# Humi_IOT.net
KiCad netlist of a schematic drawn in Altium Designer
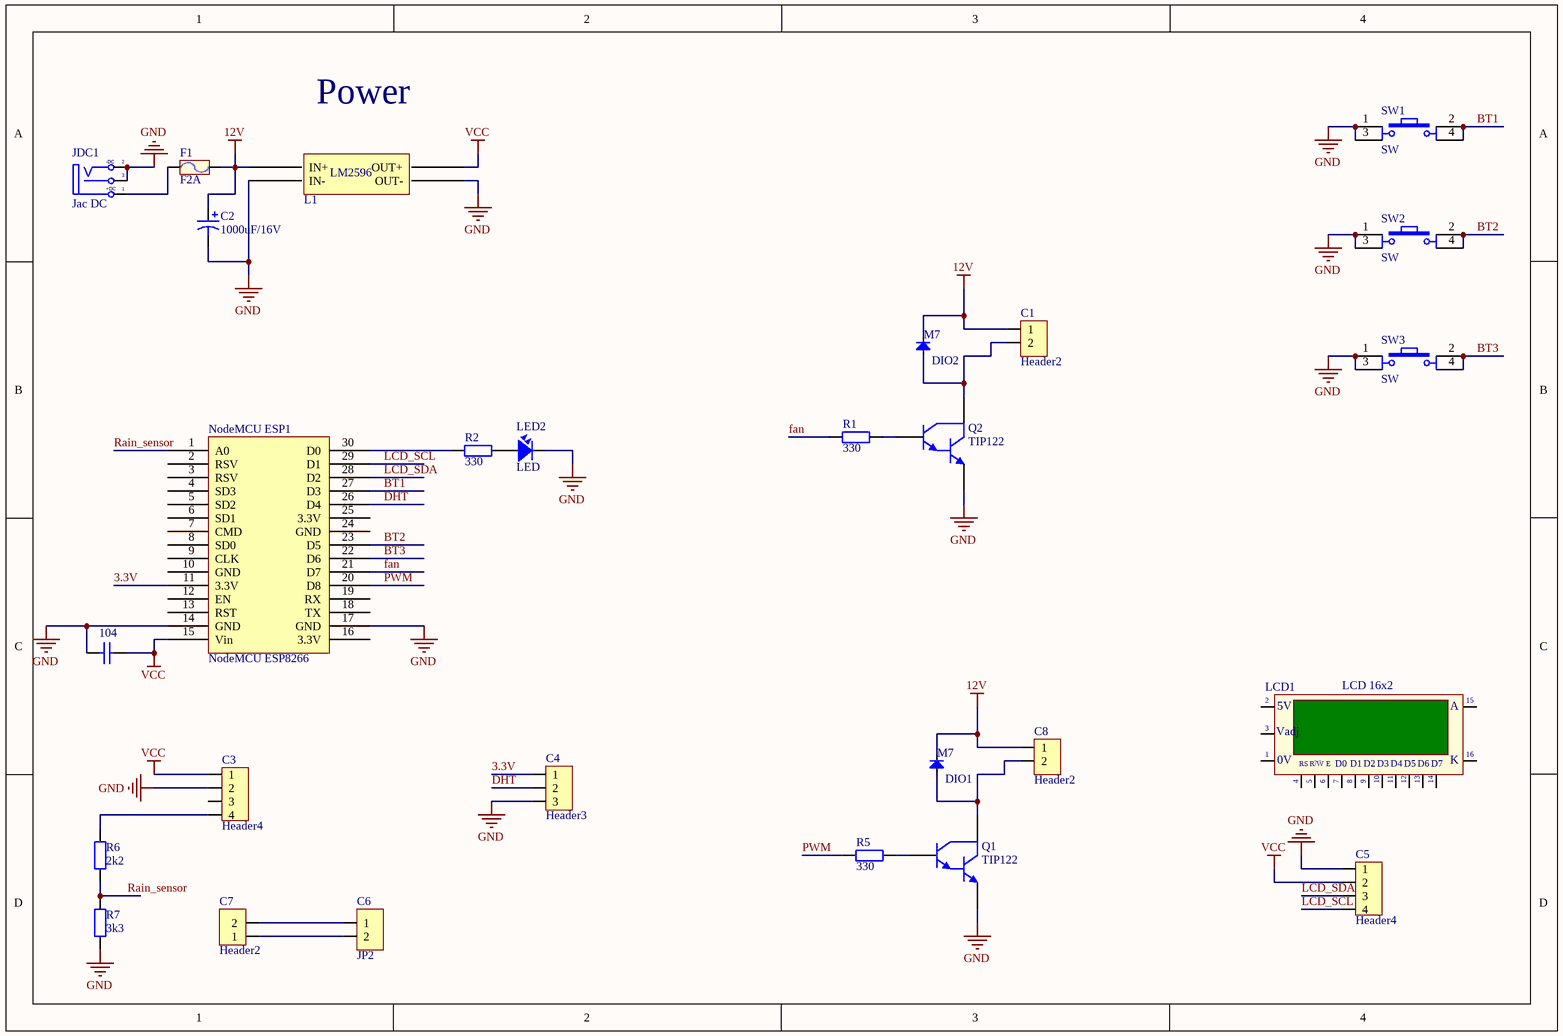
[diagram p0: Humi_IOT.SchDoc]

(export (version "E")
  (design (tool "Eeschema 10.0.6"))
  (components
    (comp (ref "104")
      (value "Capacitor Ceramic")
      (footprint "C0805")
      (description "Capacitor")
      (fields (field (name "PUBLISHER") "Altium Limited"))
      (libsource (lib "My Library") (part "CapSMD"))
    )
    (comp (ref "C1")
      (value "Header2")
      (footprint "Header2")
      (description "Header IDC, 2 x 1 Pin Vertical 2.54mm Pitch (Non-Boxed, Male)")
      (fields
        (field (name "MANUFACTURER") "Würth Elektronik eiSos GmbH")
        (field (name "PARTNO") "613002143121")
        (field (name "CREATED BY") "Karrer Zheng")
      )
      (libsource (lib "My Library") (part "Header2"))
    )
    (comp (ref "C2")
      (value "1000uF/16V")
      (footprint "C10mm")
      (description "Polarized Capacitor (Axial)")
      (fields (field (name "PUBLISHER") "Altium Limited"))
      (libsource (lib "My Library") (part "Cap Pol 12mm"))
    )
    (comp (ref "C3")
      (value "Header4")
      (footprint "HDR4")
      (description "Header IDC, 4 x 1 Pin Vertical 2.54mm Pitch (Non-Boxed, Male)")
      (fields
        (field (name "MANUFACTURER") "Würth Elektronik eiSos GmbH")
        (field (name "PARTNO") "613002143121")
        (field (name "CREATED BY") "Karrer Zheng")
      )
      (libsource (lib "My Library") (part "Header4"))
    )
    (comp (ref "C4")
      (value "Header3")
      (footprint "Header3")
      (description "Header IDC, 3 x 1 Pin Vertical 2.54mm Pitch (Non-Boxed, Male)")
      (fields
        (field (name "MANUFACTURER") "Würth Elektronik eiSos GmbH")
        (field (name "PARTNO") "613002143121")
        (field (name "CREATED BY") "Karrer Zheng")
      )
      (libsource (lib "My Library") (part "Header3"))
    )
    (comp (ref "C5")
      (value "Header4")
      (footprint "HDR4")
      (description "Header IDC, 4 x 1 Pin Vertical 2.54mm Pitch (Non-Boxed, Male)")
      (fields
        (field (name "MANUFACTURER") "Würth Elektronik eiSos GmbH")
        (field (name "PARTNO") "613002143121")
        (field (name "CREATED BY") "Karrer Zheng")
      )
      (libsource (lib "My Library") (part "Header4"))
    )
    (comp (ref "C6")
      (value "JP2")
      (footprint "JP2-C1T")
      (description "WR-PHD 2.54 mm Angled Socket Header")
      (fields
        (field (name "MANUFACTURER") "Würth Elektronik eiSos GmbH")
        (field (name "PARTNO") "613002143121")
        (field (name "CREATED BY") "Karrer Zheng")
      )
      (libsource (lib "My Library") (part "JP2"))
    )
    (comp (ref "C7")
      (value "Header2")
      (footprint "Header2")
      (description "Header IDC, 2 x 1 Pin Vertical 2.54mm Pitch (Non-Boxed, Male)")
      (fields
        (field (name "MANUFACTURER") "Würth Elektronik eiSos GmbH")
        (field (name "PARTNO") "613002143121")
        (field (name "CREATED BY") "Karrer Zheng")
      )
      (libsource (lib "") (part "Header2_1"))
    )
    (comp (ref "C8")
      (value "Header2")
      (footprint "Header2")
      (description "Header IDC, 2 x 1 Pin Vertical 2.54mm Pitch (Non-Boxed, Male)")
      (fields
        (field (name "MANUFACTURER") "Würth Elektronik eiSos GmbH")
        (field (name "PARTNO") "613002143121")
        (field (name "CREATED BY") "Karrer Zheng")
      )
      (libsource (lib "My Library") (part "Header2"))
    )
    (comp (ref "DIO1")
      (value "M7")
      (footprint "DIO-SMD-106")
      (description "Default Diode")
      (fields (field (name "PUBLISHER") "Altium Limited"))
      (libsource (lib "My Library (1)") (part "Diode SMD"))
    )
    (comp (ref "DIO2")
      (value "M7")
      (footprint "DIO-SMD-106")
      (description "Default Diode")
      (fields (field (name "PUBLISHER") "Altium Limited"))
      (libsource (lib "My Library (1)") (part "Diode SMD"))
    )
    (comp (ref "F1")
      (value "F2A")
      (footprint "Fuse")
      (description "Fuse")
      (fields (field (name "DESIGNED BY") "VanDungEvn"))
      (libsource (lib "My Library") (part "Fuse"))
    )
    (comp (ref "JDC1")
      (value "Jac DC")
      (footprint "DC-IN")
      (description "Jac DC input")
      (libsource (lib "My Library") (part "DCIN"))
    )
    (comp (ref "L1")
      (value "BUCK_LM2596")
      (footprint "BUCK_LM2596")
      (libsource (lib "BUCK_LM2596_Sch") (part "BUCK_LM2596"))
    )
    (comp (ref "LCD1")
      (value "LCD 16x2")
      (footprint "LCD16X2N")
      (libsource (lib "My library altium") (part "LCD"))
    )
    (comp (ref "LED2")
      (value "LED")
      (footprint "LED-5 GRe")
      (description "LED Single colour Green and Red")
      (libsource (lib "My Library") (part "LED"))
    )
    (comp (ref "NodeMCU ESP1")
      (value "NodeMCU ESP8266")
      (footprint "NodeMCU ESP8266")
      (libsource (lib "Phieu_Du") (part "NodeMCU ESP8266"))
    )
    (comp (ref "Q1")
      (value "TIP122")
      (footprint "QTO-220")
      (description "Darlington Silicon Power NPN Transistor, 8 Amp, 100 Volts and 65 Watts")
      (libsource (lib "My Library (1)") (part "TIP122"))
    )
    (comp (ref "Q2")
      (value "TIP122")
      (footprint "QTO-220")
      (description "Darlington Silicon Power NPN Transistor, 8 Amp, 100 Volts and 65 Watts")
      (libsource (lib "My Library (1)") (part "TIP122"))
    )
    (comp (ref "R1")
      (value "330")
      (footprint "DIEN TRO 0805")
      (description "Resistor SMD 0805")
      (fields (field (name "PUBLISHER") "Altium Limited"))
      (libsource (lib "My Library (1)") (part "R0805"))
    )
    (comp (ref "R2")
      (value "330")
      (footprint "DIEN TRO 0805")
      (description "Resistor SMD 0805")
      (fields (field (name "PUBLISHER") "Altium Limited"))
      (libsource (lib "My Library (1)") (part "R0805"))
    )
    (comp (ref "R5")
      (value "330")
      (footprint "DIEN TRO 0805")
      (description "Resistor SMD 0805")
      (fields (field (name "PUBLISHER") "Altium Limited"))
      (libsource (lib "My Library (1)") (part "R0805"))
    )
    (comp (ref "R6")
      (value "2k2")
      (footprint "DIEN TRO 0805")
      (description "Resistor SMD 0805")
      (fields (field (name "PUBLISHER") "Altium Limited"))
      (libsource (lib "") (part "R0805_1"))
    )
    (comp (ref "R7")
      (value "3k3")
      (footprint "DIEN TRO 0805")
      (description "Resistor SMD 0805")
      (fields (field (name "PUBLISHER") "Altium Limited"))
      (libsource (lib "") (part "R0805_1"))
    )
    (comp (ref "SW1")
      (value "SW")
      (footprint "SW4")
      (description "Switch button 4 pin")
      (libsource (lib "My Library (1)") (part "SW4"))
    )
    (comp (ref "SW2")
      (value "SW")
      (footprint "SW4")
      (description "Switch button 4 pin")
      (libsource (lib "My Library (1)") (part "SW4"))
    )
    (comp (ref "SW3")
      (value "SW")
      (footprint "SW4")
      (description "Switch button 4 pin")
      (libsource (lib "My Library (1)") (part "SW4"))
    )
  )
  (nets
    (net (code "1") (name "/3.3V") (class "Default")
      (node (ref "C4") (pin "1") (pinfunction "1_1") (pintype "passive"))
      (node (ref "NodeMCU ESP1") (pin "11") (pinfunction "3.3V_11") (pintype "passive"))
    )
    (net (code "2") (name "/BT1") (class "Default")
      (node (ref "NodeMCU ESP1") (pin "27") (pinfunction "D3_27") (pintype "passive"))
      (node (ref "SW1") (pin "2") (pintype "passive"))
      (node (ref "SW1") (pin "4") (pintype "passive"))
    )
    (net (code "3") (name "/BT2") (class "Default")
      (node (ref "NodeMCU ESP1") (pin "23") (pinfunction "D5_23") (pintype "passive"))
      (node (ref "SW2") (pin "2") (pintype "passive"))
      (node (ref "SW2") (pin "4") (pintype "passive"))
    )
    (net (code "4") (name "/BT3") (class "Default")
      (node (ref "NodeMCU ESP1") (pin "22") (pinfunction "D6_22") (pintype "passive"))
      (node (ref "SW3") (pin "2") (pintype "passive"))
      (node (ref "SW3") (pin "4") (pintype "passive"))
    )
    (net (code "5") (name "/DHT") (class "Default")
      (node (ref "C4") (pin "2") (pinfunction "2_2") (pintype "passive"))
      (node (ref "NodeMCU ESP1") (pin "26") (pinfunction "D4_26") (pintype "passive"))
    )
    (net (code "6") (name "/LCD_SCL") (class "Default")
      (node (ref "C5") (pin "4") (pinfunction "4_4") (pintype "passive"))
      (node (ref "NodeMCU ESP1") (pin "29") (pinfunction "D1_29") (pintype "passive"))
    )
    (net (code "7") (name "/LCD_SDA") (class "Default")
      (node (ref "C5") (pin "3") (pinfunction "3_3") (pintype "passive"))
      (node (ref "NodeMCU ESP1") (pin "28") (pinfunction "D2_28") (pintype "passive"))
    )
    (net (code "8") (name "/PWM") (class "Default")
      (node (ref "NodeMCU ESP1") (pin "20") (pinfunction "D8_20") (pintype "passive"))
      (node (ref "R5") (pin "2") (pinfunction "2_2") (pintype "passive"))
    )
    (net (code "9") (name "/Rain_sensor") (class "Default")
      (node (ref "NodeMCU ESP1") (pin "1") (pinfunction "A0_1") (pintype "passive"))
      (node (ref "R6") (pin "2") (pinfunction "2_2") (pintype "passive"))
      (node (ref "R7") (pin "1") (pinfunction "1_1") (pintype "passive"))
    )
    (net (code "10") (name "/fan") (class "Default")
      (node (ref "NodeMCU ESP1") (pin "21") (pinfunction "D7_21") (pintype "passive"))
      (node (ref "R1") (pin "2") (pinfunction "2_2") (pintype "passive"))
    )
    (net (code "11") (name "12V") (class "Default")
      (node (ref "C1") (pin "1") (pinfunction "1_1") (pintype "passive"))
      (node (ref "C2") (pin "1") (pinfunction "1_1") (pintype "passive"))
      (node (ref "C8") (pin "1") (pinfunction "1_1") (pintype "passive"))
      (node (ref "DIO1") (pin "2") (pinfunction "K_2") (pintype "passive"))
      (node (ref "DIO2") (pin "2") (pinfunction "K_2") (pintype "passive"))
      (node (ref "F1") (pin "2") (pinfunction "2_2") (pintype "passive"))
      (node (ref "L1") (pin "1") (pinfunction "IN+_1") (pintype "passive"))
    )
    (net (code "12") (name "GND") (class "Default")
      (node (ref "104") (pin "1") (pinfunction "1_1") (pintype "passive"))
      (node (ref "C2") (pin "2") (pinfunction "2_2") (pintype "passive"))
      (node (ref "C3") (pin "2") (pinfunction "2_2") (pintype "passive"))
      (node (ref "C4") (pin "3") (pinfunction "3_3") (pintype "passive"))
      (node (ref "C5") (pin "1") (pinfunction "1_1") (pintype "passive"))
      (node (ref "JDC1") (pin "2") (pinfunction "TN_2") (pintype "passive"))
      (node (ref "JDC1") (pin "3") (pinfunction "S_3") (pintype "power_in"))
      (node (ref "L1") (pin "2") (pinfunction "IN-_2") (pintype "passive"))
      (node (ref "L1") (pin "3") (pinfunction "OUT-_3") (pintype "passive"))
      (node (ref "LED2") (pin "2") (pinfunction "2_2") (pintype "passive"))
      (node (ref "NodeMCU ESP1") (pin "14") (pinfunction "GND_14") (pintype "passive"))
      (node (ref "NodeMCU ESP1") (pin "17") (pinfunction "GND_17") (pintype "passive"))
      (node (ref "Q1") (pin "3") (pinfunction "E_3") (pintype "passive"))
      (node (ref "Q2") (pin "3") (pinfunction "E_3") (pintype "passive"))
      (node (ref "R7") (pin "2") (pinfunction "2_2") (pintype "passive"))
      (node (ref "SW1") (pin "1") (pintype "passive"))
      (node (ref "SW1") (pin "3") (pintype "passive"))
      (node (ref "SW2") (pin "1") (pintype "passive"))
      (node (ref "SW2") (pin "3") (pintype "passive"))
      (node (ref "SW3") (pin "1") (pintype "passive"))
      (node (ref "SW3") (pin "3") (pintype "passive"))
    )
    (net (code "13") (name "Net-(C3-Pad4)") (class "Default")
      (node (ref "C3") (pin "4") (pinfunction "4_4") (pintype "passive"))
      (node (ref "R6") (pin "1") (pinfunction "1_1") (pintype "passive"))
    )
    (net (code "14") (name "Net-(C6-Pad1)") (class "Default")
      (node (ref "C6") (pin "1") (pinfunction "1_1") (pintype "passive"))
      (node (ref "C7") (pin "2") (pinfunction "2_2") (pintype "passive"))
    )
    (net (code "15") (name "Net-(C6-Pad2)") (class "Default")
      (node (ref "C6") (pin "2") (pinfunction "2_2") (pintype "passive"))
      (node (ref "C7") (pin "1") (pinfunction "1_1") (pintype "passive"))
    )
    (net (code "16") (name "Net-(DIO1-A)") (class "Default")
      (node (ref "C8") (pin "2") (pinfunction "2_2") (pintype "passive"))
      (node (ref "DIO1") (pin "1") (pinfunction "A_1") (pintype "passive"))
      (node (ref "Q1") (pin "2") (pinfunction "C_2") (pintype "passive"))
    )
    (net (code "17") (name "Net-(DIO2-A)") (class "Default")
      (node (ref "C1") (pin "2") (pinfunction "2_2") (pintype "passive"))
      (node (ref "DIO2") (pin "1") (pinfunction "A_1") (pintype "passive"))
      (node (ref "Q2") (pin "2") (pinfunction "C_2") (pintype "passive"))
    )
    (net (code "18") (name "Net-(JDC1-T)") (class "Default")
      (node (ref "F1") (pin "1") (pinfunction "1_1") (pintype "passive"))
      (node (ref "JDC1") (pin "1") (pinfunction "T_1") (pintype "passive"))
    )
    (net (code "19") (name "Net-(LED2-Pad1)") (class "Default")
      (node (ref "LED2") (pin "1") (pinfunction "1_1") (pintype "passive"))
      (node (ref "R2") (pin "1") (pinfunction "1_1") (pintype "passive"))
    )
    (net (code "20") (name "Net-(NodeMCU ESP1-D0)") (class "Default")
      (node (ref "NodeMCU ESP1") (pin "30") (pinfunction "D0_30") (pintype "passive"))
      (node (ref "R2") (pin "2") (pinfunction "2_2") (pintype "passive"))
    )
    (net (code "21") (name "Net-(Q1-B)") (class "Default")
      (node (ref "Q1") (pin "1") (pinfunction "B_1") (pintype "passive"))
      (node (ref "R5") (pin "1") (pinfunction "1_1") (pintype "passive"))
    )
    (net (code "22") (name "Net-(Q2-B)") (class "Default")
      (node (ref "Q2") (pin "1") (pinfunction "B_1") (pintype "passive"))
      (node (ref "R1") (pin "1") (pinfunction "1_1") (pintype "passive"))
    )
    (net (code "23") (name "VCC") (class "Default")
      (node (ref "104") (pin "2") (pinfunction "2_2") (pintype "passive"))
      (node (ref "C3") (pin "1") (pinfunction "1_1") (pintype "passive"))
      (node (ref "C5") (pin "2") (pinfunction "2_2") (pintype "passive"))
      (node (ref "L1") (pin "4") (pinfunction "OUT+_4") (pintype "passive"))
      (node (ref "NodeMCU ESP1") (pin "15") (pinfunction "Vin_15") (pintype "passive"))
    )
    (net (code "24") (name "unconnected-(C3-Pad3)") (class "Default")
      (node (ref "C3") (pin "3") (pinfunction "3_3") (pintype "passive"))
    )
    (net (code "25") (name "unconnected-(LCD1-A-Pad15)") (class "Default")
      (node (ref "LCD1") (pin "15") (pinfunction "A_15") (pintype "passive"))
    )
    (net (code "26") (name "unconnected-(LCD1-D0-Pad7)") (class "Default")
      (node (ref "LCD1") (pin "7") (pinfunction "D0_7") (pintype "passive"))
    )
    (net (code "27") (name "unconnected-(LCD1-D1-Pad8)") (class "Default")
      (node (ref "LCD1") (pin "8") (pinfunction "D1_8") (pintype "passive"))
    )
    (net (code "28") (name "unconnected-(LCD1-D2-Pad9)") (class "Default")
      (node (ref "LCD1") (pin "9") (pinfunction "D2_9") (pintype "passive"))
    )
    (net (code "29") (name "unconnected-(LCD1-D3-Pad10)") (class "Default")
      (node (ref "LCD1") (pin "10") (pinfunction "D3_10") (pintype "passive"))
    )
    (net (code "30") (name "unconnected-(LCD1-D4-Pad11)") (class "Default")
      (node (ref "LCD1") (pin "11") (pinfunction "D4_11") (pintype "passive"))
    )
    (net (code "31") (name "unconnected-(LCD1-D5-Pad12)") (class "Default")
      (node (ref "LCD1") (pin "12") (pinfunction "D5_12") (pintype "passive"))
    )
    (net (code "32") (name "unconnected-(LCD1-D6-Pad13)") (class "Default")
      (node (ref "LCD1") (pin "13") (pinfunction "D6_13") (pintype "passive"))
    )
    (net (code "33") (name "unconnected-(LCD1-D7-Pad14)") (class "Default")
      (node (ref "LCD1") (pin "14") (pinfunction "D7_14") (pintype "passive"))
    )
    (net (code "34") (name "unconnected-(LCD1-GND-Pad1)") (class "Default")
      (node (ref "LCD1") (pin "1") (pinfunction "GND_1") (pintype "passive"))
    )
    (net (code "35") (name "unconnected-(LCD1-K-Pad16)") (class "Default")
      (node (ref "LCD1") (pin "16") (pinfunction "K_16") (pintype "passive"))
    )
    (net (code "36") (name "unconnected-(LCD1-RS-Pad4)") (class "Default")
      (node (ref "LCD1") (pin "4") (pinfunction "RS_4") (pintype "passive"))
    )
    (net (code "37") (name "unconnected-(LCD1-R{slash}~{W}-Pad5)") (class "Default")
      (node (ref "LCD1") (pin "5") (pinfunction "R/~{W}_5") (pintype "passive"))
    )
    (net (code "38") (name "unconnected-(LCD1-VAdj-Pad3)") (class "Default")
      (node (ref "LCD1") (pin "3") (pinfunction "VAdj_3") (pintype "passive"))
    )
    (net (code "39") (name "unconnected-(LCD1-VDD-Pad2)") (class "Default")
      (node (ref "LCD1") (pin "2") (pinfunction "VDD_2") (pintype "passive"))
    )
    (net (code "40") (name "unconnected-(LCD1-~{EN}-Pad6)") (class "Default")
      (node (ref "LCD1") (pin "6") (pinfunction "~{EN}_6") (pintype "passive"))
    )
    (net (code "41") (name "unconnected-(NodeMCU ESP1-3.3V-Pad16)") (class "Default")
      (node (ref "NodeMCU ESP1") (pin "16") (pinfunction "3.3V_16") (pintype "passive"))
    )
    (net (code "42") (name "unconnected-(NodeMCU ESP1-3.3V-Pad25)") (class "Default")
      (node (ref "NodeMCU ESP1") (pin "25") (pinfunction "3.3V_25") (pintype "passive"))
    )
    (net (code "43") (name "unconnected-(NodeMCU ESP1-CLK-Pad9)") (class "Default")
      (node (ref "NodeMCU ESP1") (pin "9") (pinfunction "CLK_9") (pintype "passive"))
    )
    (net (code "44") (name "unconnected-(NodeMCU ESP1-CMD-Pad7)") (class "Default")
      (node (ref "NodeMCU ESP1") (pin "7") (pinfunction "CMD_7") (pintype "passive"))
    )
    (net (code "45") (name "unconnected-(NodeMCU ESP1-EN-Pad12)") (class "Default")
      (node (ref "NodeMCU ESP1") (pin "12") (pinfunction "EN_12") (pintype "passive"))
    )
    (net (code "46") (name "unconnected-(NodeMCU ESP1-GND-Pad10)") (class "Default")
      (node (ref "NodeMCU ESP1") (pin "10") (pinfunction "GND_10") (pintype "passive"))
    )
    (net (code "47") (name "unconnected-(NodeMCU ESP1-GND-Pad24)") (class "Default")
      (node (ref "NodeMCU ESP1") (pin "24") (pinfunction "GND_24") (pintype "passive"))
    )
    (net (code "48") (name "unconnected-(NodeMCU ESP1-RST-Pad13)") (class "Default")
      (node (ref "NodeMCU ESP1") (pin "13") (pinfunction "RST_13") (pintype "passive"))
    )
    (net (code "49") (name "unconnected-(NodeMCU ESP1-RSV-Pad2)") (class "Default")
      (node (ref "NodeMCU ESP1") (pin "2") (pinfunction "RSV_2") (pintype "passive"))
    )
    (net (code "50") (name "unconnected-(NodeMCU ESP1-RSV-Pad3)") (class "Default")
      (node (ref "NodeMCU ESP1") (pin "3") (pinfunction "RSV_3") (pintype "passive"))
    )
    (net (code "51") (name "unconnected-(NodeMCU ESP1-RX-Pad19)") (class "Default")
      (node (ref "NodeMCU ESP1") (pin "19") (pinfunction "RX_19") (pintype "passive"))
    )
    (net (code "52") (name "unconnected-(NodeMCU ESP1-SD0-Pad8)") (class "Default")
      (node (ref "NodeMCU ESP1") (pin "8") (pinfunction "SD0_8") (pintype "passive"))
    )
    (net (code "53") (name "unconnected-(NodeMCU ESP1-SD1-Pad6)") (class "Default")
      (node (ref "NodeMCU ESP1") (pin "6") (pinfunction "SD1_6") (pintype "passive"))
    )
    (net (code "54") (name "unconnected-(NodeMCU ESP1-SD2-Pad5)") (class "Default")
      (node (ref "NodeMCU ESP1") (pin "5") (pinfunction "SD2_5") (pintype "passive"))
    )
    (net (code "55") (name "unconnected-(NodeMCU ESP1-SD3-Pad4)") (class "Default")
      (node (ref "NodeMCU ESP1") (pin "4") (pinfunction "SD3_4") (pintype "passive"))
    )
    (net (code "56") (name "unconnected-(NodeMCU ESP1-TX-Pad18)") (class "Default")
      (node (ref "NodeMCU ESP1") (pin "18") (pinfunction "TX_18") (pintype "passive"))
    )
  )
)
